# MicrocontrollerBoard_V0_2.net
KiCad netlist of a schematic drawn in EAGLE
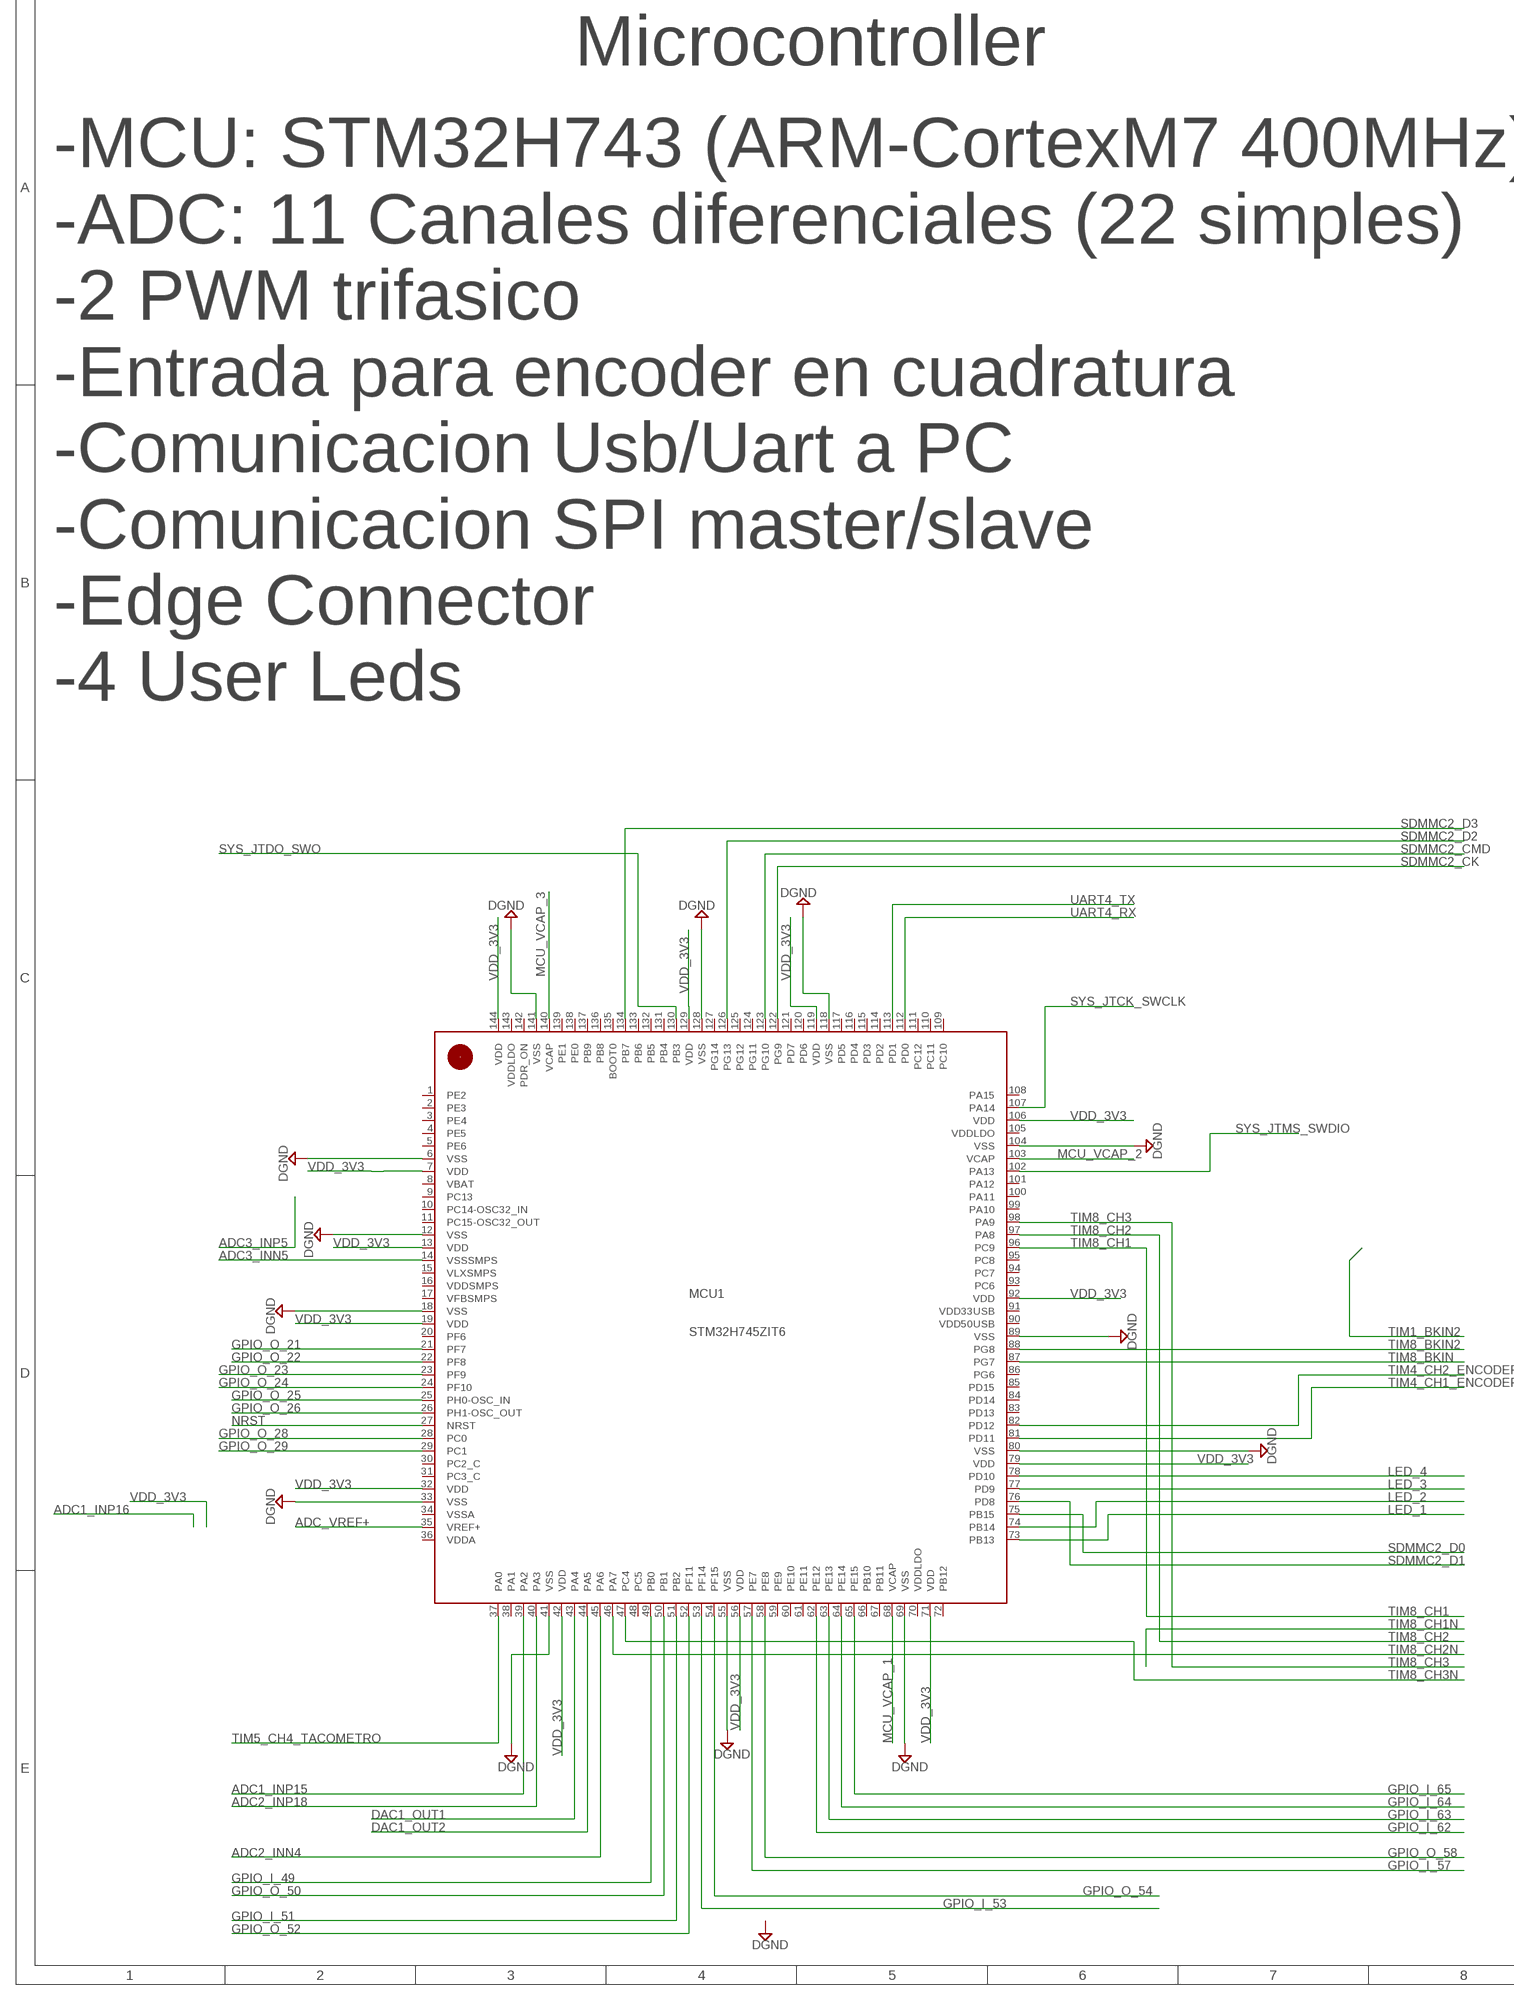
[diagram p0: schematic, sheet 1, part 1 of 2]
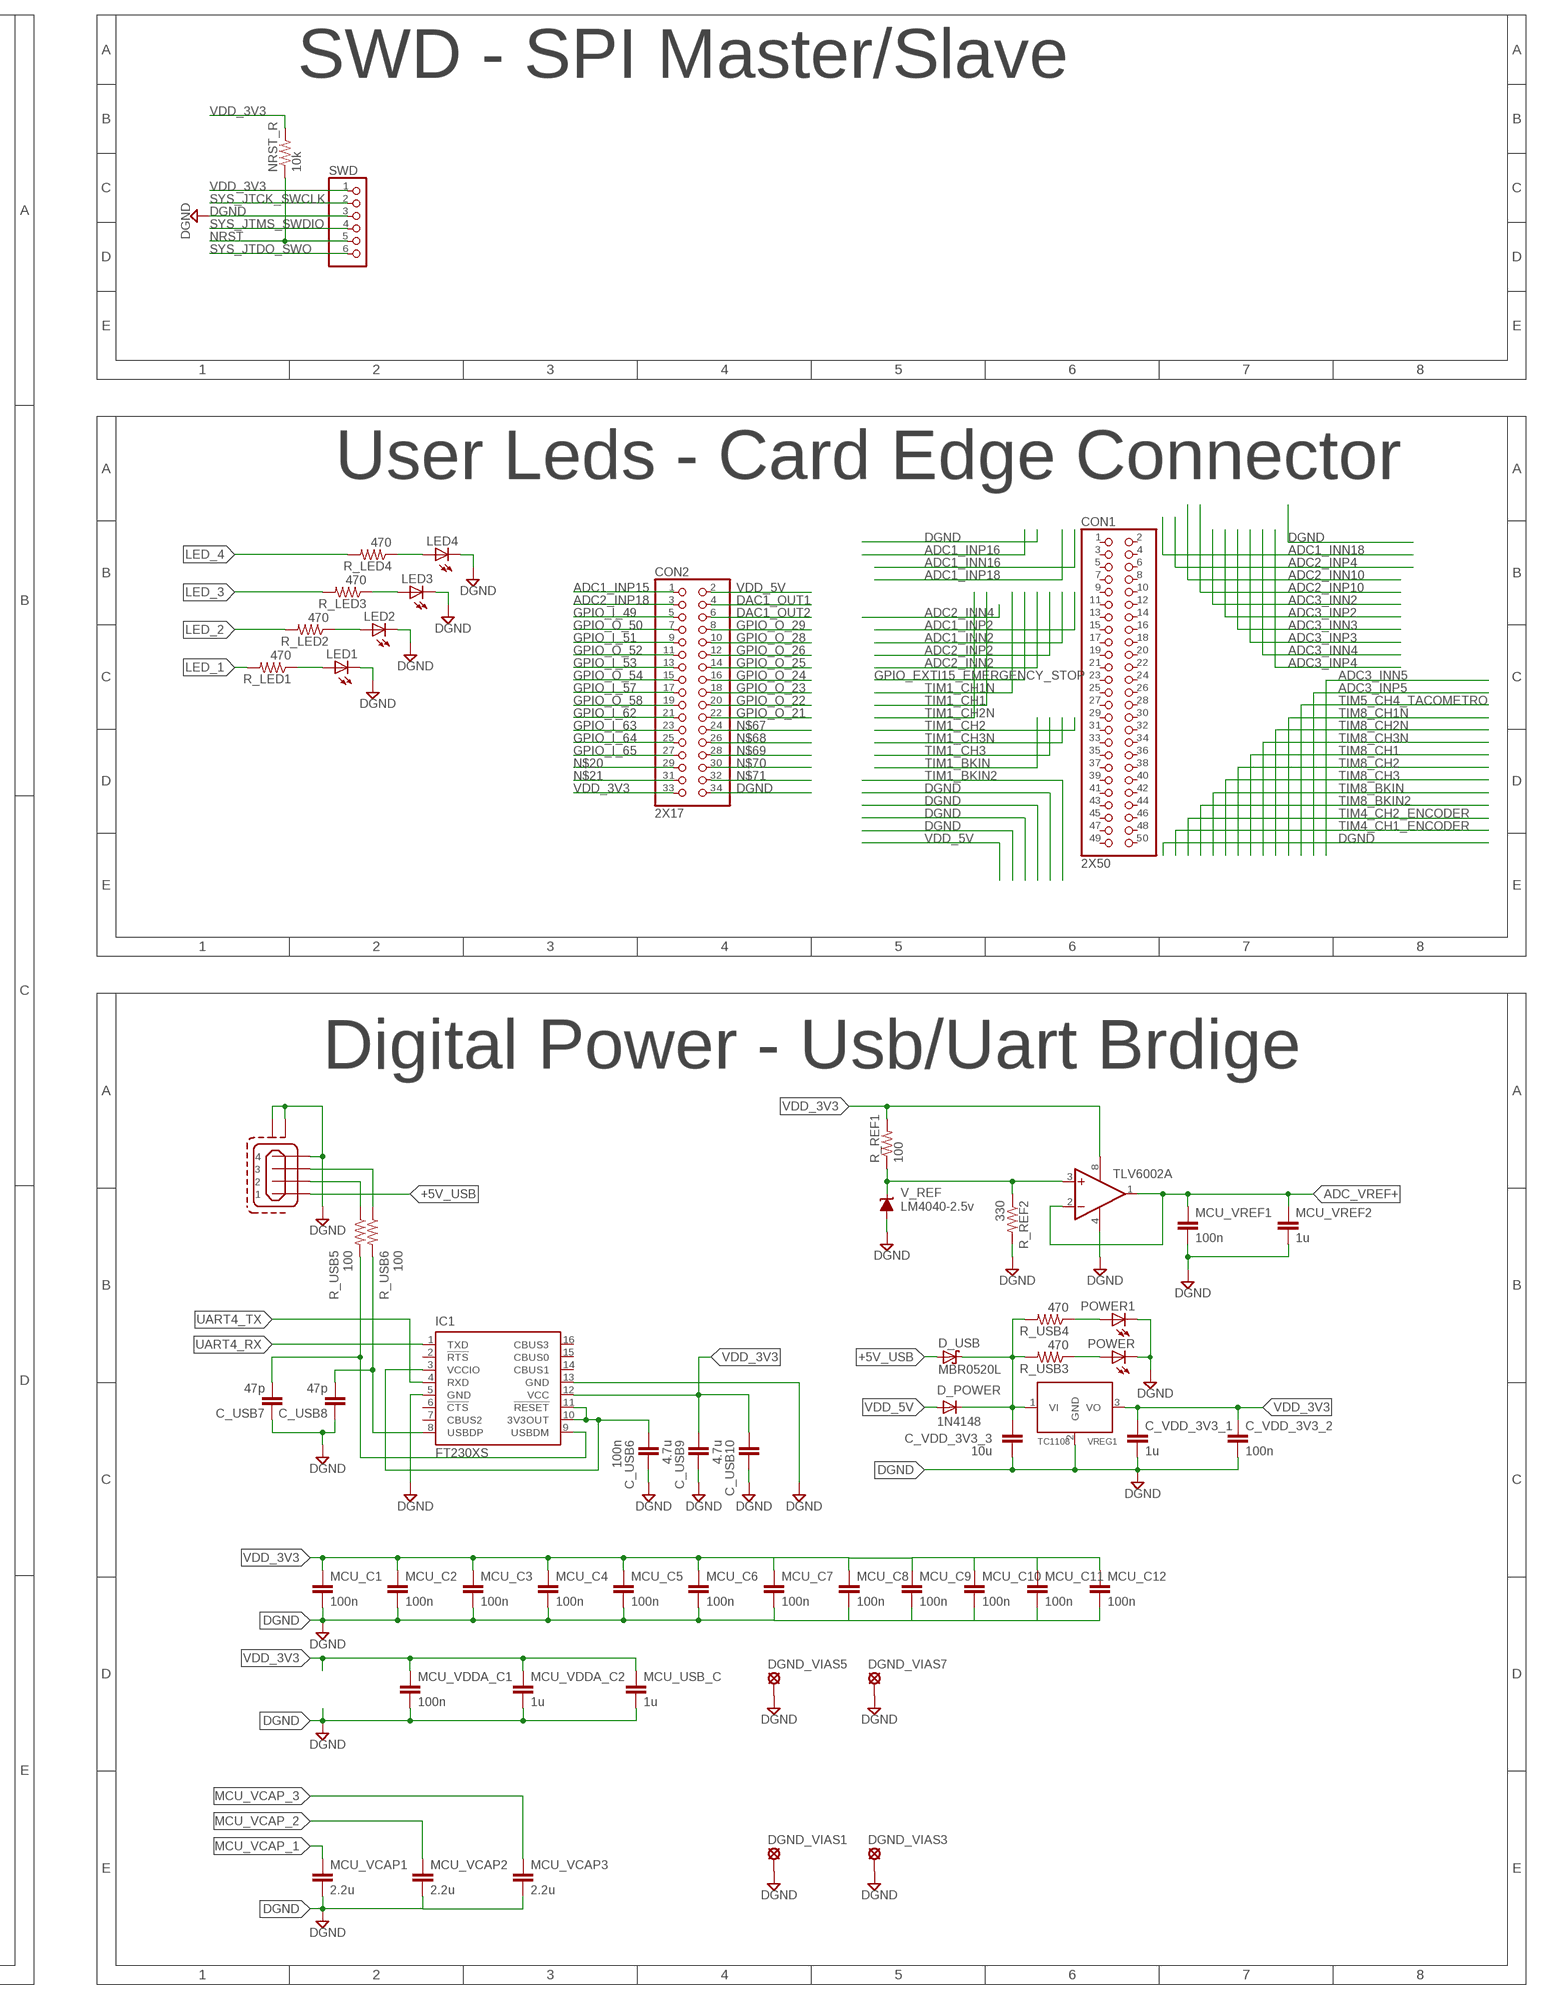
[diagram p1: schematic, sheet 1, part 2 of 2]

(export (version "E")
  (design (tool "Eeschema 10.0.6"))
  (components
    (comp (ref "CON1")
      (value "2X50")
      (footprint "eagle-import:2X25")
      (libsource (lib "eagle-import") (part "2X50"))
    )
    (comp (ref "CON2")
      (value "2X17")
      (footprint "eagle-import:2X17")
      (libsource (lib "eagle-import") (part "2X17"))
    )
    (comp (ref "C_USB6")
      (value "100n")
      (footprint "eagle-import:C0402")
      (libsource (lib "eagle-import") (part "C-EUC0402"))
    )
    (comp (ref "C_USB7")
      (value "47p")
      (footprint "eagle-import:C0402")
      (libsource (lib "eagle-import") (part "C-EUC0402"))
    )
    (comp (ref "C_USB8")
      (value "47p")
      (footprint "eagle-import:C0402")
      (libsource (lib "eagle-import") (part "C-EUC0402"))
    )
    (comp (ref "C_USB9")
      (value "4.7u")
      (footprint "eagle-import:C0402")
      (libsource (lib "eagle-import") (part "C-EUC0402"))
    )
    (comp (ref "C_USB10")
      (value "4.7u")
      (footprint "eagle-import:C0402")
      (libsource (lib "eagle-import") (part "C-EUC0402"))
    )
    (comp (ref "C_VDD_3V3_1")
      (value "1u")
      (footprint "eagle-import:C0603K")
      (libsource (lib "eagle-import") (part "C-EUC0603K"))
    )
    (comp (ref "C_VDD_3V3_2")
      (value "100n")
      (footprint "eagle-import:C0603K")
      (libsource (lib "eagle-import") (part "C-EUC0603K"))
    )
    (comp (ref "C_VDD_3V3_3")
      (value "10u")
      (footprint "eagle-import:C0603K")
      (libsource (lib "eagle-import") (part "C-EUC0603K"))
    )
    (comp (ref "DGND_VIAS1")
      (value "LSP10")
      (footprint "eagle-import:LSP10")
      (libsource (lib "eagle-import") (part "LSP10"))
    )
    (comp (ref "DGND_VIAS3")
      (value "LSP10")
      (footprint "eagle-import:LSP10")
      (libsource (lib "eagle-import") (part "LSP10"))
    )
    (comp (ref "DGND_VIAS5")
      (value "LSP10")
      (footprint "eagle-import:LSP10")
      (libsource (lib "eagle-import") (part "LSP10"))
    )
    (comp (ref "DGND_VIAS7")
      (value "LSP10")
      (footprint "eagle-import:LSP10")
      (libsource (lib "eagle-import") (part "LSP10"))
    )
    (comp (ref "D_POWER")
      (value "1N4148")
      (footprint "eagle-import:SMA-DO214AC")
      (libsource (lib "eagle-import") (part "GF1"))
    )
    (comp (ref "D_USB")
      (value "MBR0520L")
      (footprint "eagle-import:SOD-123")
      (libsource (lib "eagle-import") (part "MBR0520L"))
    )
    (comp (ref "IC1")
      (value "FT230XS")
      (footprint "eagle-import:SSOP16")
      (libsource (lib "eagle-import") (part "FT230XS"))
    )
    (comp (ref "LED1")
      (value "LEDCHIPLED_0805")
      (footprint "eagle-import:CHIPLED_0805")
      (libsource (lib "eagle-import") (part "LEDCHIPLED_0805"))
    )
    (comp (ref "LED2")
      (value "LEDCHIPLED_0805")
      (footprint "eagle-import:CHIPLED_0805")
      (libsource (lib "eagle-import") (part "LEDCHIPLED_0805"))
    )
    (comp (ref "LED3")
      (value "LEDCHIPLED_0805")
      (footprint "eagle-import:CHIPLED_0805")
      (libsource (lib "eagle-import") (part "LEDCHIPLED_0805"))
    )
    (comp (ref "LED4")
      (value "LEDCHIPLED_0805")
      (footprint "eagle-import:CHIPLED_0805")
      (libsource (lib "eagle-import") (part "LEDCHIPLED_0805"))
    )
    (comp (ref "MCU1")
      (value "STM32H745ZIT6144")
      (footprint "eagle-import:LQFP144")
      (libsource (lib "eagle-import") (part "STM32H745ZIT6144"))
    )
    (comp (ref "MCU_C1")
      (value "100n")
      (footprint "eagle-import:C0402")
      (libsource (lib "eagle-import") (part "C-EUC0402"))
    )
    (comp (ref "MCU_C2")
      (value "100n")
      (footprint "eagle-import:C0402")
      (libsource (lib "eagle-import") (part "C-EUC0402"))
    )
    (comp (ref "MCU_C3")
      (value "100n")
      (footprint "eagle-import:C0402")
      (libsource (lib "eagle-import") (part "C-EUC0402"))
    )
    (comp (ref "MCU_C4")
      (value "100n")
      (footprint "eagle-import:C0402")
      (libsource (lib "eagle-import") (part "C-EUC0402"))
    )
    (comp (ref "MCU_C5")
      (value "100n")
      (footprint "eagle-import:C0402")
      (libsource (lib "eagle-import") (part "C-EUC0402"))
    )
    (comp (ref "MCU_C6")
      (value "100n")
      (footprint "eagle-import:C0402")
      (libsource (lib "eagle-import") (part "C-EUC0402"))
    )
    (comp (ref "MCU_C7")
      (value "100n")
      (footprint "eagle-import:C0402")
      (libsource (lib "eagle-import") (part "C-EUC0402"))
    )
    (comp (ref "MCU_C8")
      (value "100n")
      (footprint "eagle-import:C0402")
      (libsource (lib "eagle-import") (part "C-EUC0402"))
    )
    (comp (ref "MCU_C9")
      (value "100n")
      (footprint "eagle-import:C0402")
      (libsource (lib "eagle-import") (part "C-EUC0402"))
    )
    (comp (ref "MCU_C10")
      (value "100n")
      (footprint "eagle-import:C0402")
      (libsource (lib "eagle-import") (part "C-EUC0402"))
    )
    (comp (ref "MCU_C11")
      (value "100n")
      (footprint "eagle-import:C0402")
      (libsource (lib "eagle-import") (part "C-EUC0402"))
    )
    (comp (ref "MCU_C12")
      (value "100n")
      (footprint "eagle-import:C0402")
      (libsource (lib "eagle-import") (part "C-EUC0402"))
    )
    (comp (ref "MCU_USB_C")
      (value "1u")
      (footprint "eagle-import:C0402")
      (libsource (lib "eagle-import") (part "C-EUC0402"))
    )
    (comp (ref "MCU_VCAP1")
      (value "2.2u")
      (footprint "eagle-import:C0402")
      (libsource (lib "eagle-import") (part "C-EUC0402"))
    )
    (comp (ref "MCU_VCAP2")
      (value "2.2u")
      (footprint "eagle-import:C0402")
      (libsource (lib "eagle-import") (part "C-EUC0402"))
    )
    (comp (ref "MCU_VCAP3")
      (value "2.2u")
      (footprint "eagle-import:C0402")
      (libsource (lib "eagle-import") (part "C-EUC0402"))
    )
    (comp (ref "MCU_VDDA_C1")
      (value "100n")
      (footprint "eagle-import:C0402")
      (libsource (lib "eagle-import") (part "C-EUC0402"))
    )
    (comp (ref "MCU_VDDA_C2")
      (value "1u")
      (footprint "eagle-import:C0402")
      (libsource (lib "eagle-import") (part "C-EUC0402"))
    )
    (comp (ref "MCU_VREF1")
      (value "100n")
      (footprint "eagle-import:C0402")
      (libsource (lib "eagle-import") (part "C-EUC0402"))
    )
    (comp (ref "MCU_VREF2")
      (value "1u")
      (footprint "eagle-import:C0402")
      (libsource (lib "eagle-import") (part "C-EUC0402"))
    )
    (comp (ref "NRST_R")
      (value "10k")
      (footprint "eagle-import:R0402")
      (libsource (lib "eagle-import") (part "R-US_R0402"))
    )
    (comp (ref "POWER")
      (value "LEDCHIPLED_0805")
      (footprint "eagle-import:CHIPLED_0805")
      (libsource (lib "eagle-import") (part "LEDCHIPLED_0805"))
    )
    (comp (ref "POWER1")
      (value "LEDCHIPLED_0805")
      (footprint "eagle-import:CHIPLED_0805")
      (libsource (lib "eagle-import") (part "LEDCHIPLED_0805"))
    )
    (comp (ref "R_LED1")
      (value "470")
      (footprint "eagle-import:R0402")
      (libsource (lib "eagle-import") (part "R-US_R0402"))
    )
    (comp (ref "R_LED2")
      (value "470")
      (footprint "eagle-import:R0402")
      (libsource (lib "eagle-import") (part "R-US_R0402"))
    )
    (comp (ref "R_LED3")
      (value "470")
      (footprint "eagle-import:R0402")
      (libsource (lib "eagle-import") (part "R-US_R0402"))
    )
    (comp (ref "R_LED4")
      (value "470")
      (footprint "eagle-import:R0402")
      (libsource (lib "eagle-import") (part "R-US_R0402"))
    )
    (comp (ref "R_REF1")
      (value "100")
      (footprint "eagle-import:R0805")
      (libsource (lib "eagle-import") (part "R-US_R0805"))
    )
    (comp (ref "R_REF2")
      (value "330")
      (footprint "eagle-import:R0805")
      (libsource (lib "eagle-import") (part "R-US_R0805"))
    )
    (comp (ref "R_USB3")
      (value "470")
      (footprint "eagle-import:R0402")
      (libsource (lib "eagle-import") (part "R-US_R0402"))
    )
    (comp (ref "R_USB4")
      (value "470")
      (footprint "eagle-import:R0402")
      (libsource (lib "eagle-import") (part "R-US_R0402"))
    )
    (comp (ref "R_USB5")
      (value "100")
      (footprint "eagle-import:R0402")
      (libsource (lib "eagle-import") (part "R-US_R0402"))
    )
    (comp (ref "R_USB6")
      (value "100")
      (footprint "eagle-import:R0402")
      (libsource (lib "eagle-import") (part "R-US_R0402"))
    )
    (comp (ref "SWD")
      (value "PINHD-1X6/90")
      (footprint "eagle-import:1X06_90")
      (libsource (lib "eagle-import") (part "PINHD-1X6/90"))
    )
    (comp (ref "TLV6002")
      (value "TL082D")
      (footprint "eagle-import:SO08")
      (libsource (lib "eagle-import") (part "TL082D"))
    )
    (comp (ref "VREG1")
      (value "TC1108'SOT-223'")
      (footprint "eagle-import:SOT-223")
      (libsource (lib "eagle-import") (part "TC1108'SOT-223'"))
    )
    (comp (ref "V_REF")
      (value "LM4040-2.5v")
      (footprint "eagle-import:DBZ_R-PDSO-G3")
      (fields (field (name "MPN") "LM4041A12IDBZR"))
      (libsource (lib "eagle-import") (part "LM4041DBZA12"))
    )
    (comp (ref "X2")
      (value "MINI-USB_SHIELD4P-85-32004-00X")
      (footprint "eagle-import:85-32004-00X")
      (libsource (lib "eagle-import") (part "MINI-USB_SHIELD4P-85-32004-00X"))
    )
  )
  (nets
    (net (code "1") (name "+5V_USB") (class "Default")
      (node (ref "D_USB") (pin "A") (pinfunction "IN_A") (pintype "passive"))
      (node (ref "X2") (pin "1") (pinfunction "1_1") (pintype "passive"))
    )
    (net (code "6") (name "/ADC1_INP15") (class "Default")
      (node (ref "CON2") (pin "1") (pinfunction "1_1") (pintype "passive"))
      (node (ref "MCU1") (pin "39") (pinfunction "PA2_39") (pintype "bidirectional"))
    )
    (net (code "10") (name "/ADC2_INN4") (class "Default")
      (node (ref "MCU1") (pin "45") (pinfunction "PA6_45") (pintype "bidirectional"))
    )
    (net (code "15") (name "/ADC2_INP18") (class "Default")
      (node (ref "CON2") (pin "3") (pinfunction "3_3") (pintype "passive"))
      (node (ref "MCU1") (pin "40") (pinfunction "PA3_40") (pintype "bidirectional"))
    )
    (net (code "19") (name "/ADC3_INN5") (class "Default")
      (node (ref "MCU1") (pin "14") (pinfunction "VSSSMPS_14") (pintype "bidirectional"))
    )
    (net (code "24") (name "/DAC1_OUT1") (class "Default")
      (node (ref "CON2") (pin "4") (pinfunction "4_4") (pintype "passive"))
      (node (ref "MCU1") (pin "43") (pinfunction "PA4_43") (pintype "bidirectional"))
    )
    (net (code "25") (name "/DAC1_OUT2") (class "Default")
      (node (ref "CON2") (pin "6") (pinfunction "6_6") (pintype "passive"))
      (node (ref "MCU1") (pin "44") (pinfunction "PA5_44") (pintype "bidirectional"))
    )
    (net (code "27") (name "/GPIO_I_49") (class "Default")
      (node (ref "CON2") (pin "5") (pinfunction "5_5") (pintype "passive"))
      (node (ref "MCU1") (pin "49") (pinfunction "PB0_49") (pintype "bidirectional"))
    )
    (net (code "28") (name "/GPIO_I_51") (class "Default")
      (node (ref "CON2") (pin "9") (pinfunction "9_9") (pintype "passive"))
      (node (ref "MCU1") (pin "51") (pinfunction "PB2_51") (pintype "bidirectional"))
    )
    (net (code "29") (name "/GPIO_I_53") (class "Default")
      (node (ref "CON2") (pin "13") (pinfunction "13_13") (pintype "passive"))
      (node (ref "MCU1") (pin "53") (pinfunction "PF14_53") (pintype "bidirectional"))
    )
    (net (code "30") (name "/GPIO_I_57") (class "Default")
      (node (ref "CON2") (pin "17") (pinfunction "17_17") (pintype "passive"))
      (node (ref "MCU1") (pin "57") (pinfunction "PE7_57") (pintype "bidirectional"))
    )
    (net (code "31") (name "/GPIO_I_62") (class "Default")
      (node (ref "CON2") (pin "21") (pinfunction "21_21") (pintype "passive"))
      (node (ref "MCU1") (pin "62") (pinfunction "PE12_62") (pintype "bidirectional"))
    )
    (net (code "32") (name "/GPIO_I_63") (class "Default")
      (node (ref "CON2") (pin "23") (pinfunction "23_23") (pintype "passive"))
      (node (ref "MCU1") (pin "63") (pinfunction "PE13_63") (pintype "bidirectional"))
    )
    (net (code "33") (name "/GPIO_I_64") (class "Default")
      (node (ref "CON2") (pin "25") (pinfunction "25_25") (pintype "passive"))
      (node (ref "MCU1") (pin "64") (pinfunction "PE14_64") (pintype "bidirectional"))
    )
    (net (code "34") (name "/GPIO_I_65") (class "Default")
      (node (ref "CON2") (pin "27") (pinfunction "27_27") (pintype "passive"))
      (node (ref "MCU1") (pin "65") (pinfunction "PE15_65") (pintype "bidirectional"))
    )
    (net (code "35") (name "/GPIO_O_21") (class "Default")
      (node (ref "CON2") (pin "22") (pinfunction "22_22") (pintype "passive"))
      (node (ref "MCU1") (pin "21") (pinfunction "PF7_21") (pintype "bidirectional"))
    )
    (net (code "36") (name "/GPIO_O_22") (class "Default")
      (node (ref "CON2") (pin "20") (pinfunction "20_20") (pintype "passive"))
      (node (ref "MCU1") (pin "22") (pinfunction "PF8_22") (pintype "bidirectional"))
    )
    (net (code "37") (name "/GPIO_O_23") (class "Default")
      (node (ref "CON2") (pin "18") (pinfunction "18_18") (pintype "passive"))
      (node (ref "MCU1") (pin "23") (pinfunction "PF9_23") (pintype "bidirectional"))
    )
    (net (code "38") (name "/GPIO_O_24") (class "Default")
      (node (ref "CON2") (pin "16") (pinfunction "16_16") (pintype "passive"))
      (node (ref "MCU1") (pin "24") (pinfunction "PF10_24") (pintype "bidirectional"))
    )
    (net (code "39") (name "/GPIO_O_25") (class "Default")
      (node (ref "CON2") (pin "14") (pinfunction "14_14") (pintype "passive"))
      (node (ref "MCU1") (pin "25") (pinfunction "PH0-OSC_IN_25") (pintype "bidirectional"))
    )
    (net (code "40") (name "/GPIO_O_26") (class "Default")
      (node (ref "CON2") (pin "12") (pinfunction "12_12") (pintype "passive"))
      (node (ref "MCU1") (pin "26") (pinfunction "PH1-OSC_OUT_26") (pintype "bidirectional"))
    )
    (net (code "41") (name "/GPIO_O_28") (class "Default")
      (node (ref "CON2") (pin "10") (pinfunction "10_10") (pintype "passive"))
      (node (ref "MCU1") (pin "28") (pinfunction "PC0_28") (pintype "bidirectional"))
    )
    (net (code "42") (name "/GPIO_O_29") (class "Default")
      (node (ref "CON2") (pin "8") (pinfunction "8_8") (pintype "passive"))
      (node (ref "MCU1") (pin "29") (pinfunction "PC1_29") (pintype "bidirectional"))
    )
    (net (code "43") (name "/GPIO_O_50") (class "Default")
      (node (ref "CON2") (pin "7") (pinfunction "7_7") (pintype "passive"))
      (node (ref "MCU1") (pin "50") (pinfunction "PB1_50") (pintype "bidirectional"))
    )
    (net (code "44") (name "/GPIO_O_52") (class "Default")
      (node (ref "CON2") (pin "11") (pinfunction "11_11") (pintype "passive"))
      (node (ref "MCU1") (pin "52") (pinfunction "PF11_52") (pintype "bidirectional"))
    )
    (net (code "45") (name "/GPIO_O_54") (class "Default")
      (node (ref "CON2") (pin "15") (pinfunction "15_15") (pintype "passive"))
      (node (ref "MCU1") (pin "54") (pinfunction "PF15_54") (pintype "bidirectional"))
    )
    (net (code "46") (name "/GPIO_O_58") (class "Default")
      (node (ref "CON2") (pin "19") (pinfunction "19_19") (pintype "passive"))
      (node (ref "MCU1") (pin "58") (pinfunction "PE8_58") (pintype "bidirectional"))
    )
    (net (code "47") (name "/N$20") (class "Default")
      (node (ref "CON2") (pin "29") (pinfunction "29_29") (pintype "passive"))
    )
    (net (code "48") (name "/N$21") (class "Default")
      (node (ref "CON2") (pin "31") (pinfunction "31_31") (pintype "passive"))
    )
    (net (code "49") (name "/N$67") (class "Default")
      (node (ref "CON2") (pin "24") (pinfunction "24_24") (pintype "passive"))
    )
    (net (code "50") (name "/N$68") (class "Default")
      (node (ref "CON2") (pin "26") (pinfunction "26_26") (pintype "passive"))
    )
    (net (code "51") (name "/N$69") (class "Default")
      (node (ref "CON2") (pin "28") (pinfunction "28_28") (pintype "passive"))
    )
    (net (code "52") (name "/N$70") (class "Default")
      (node (ref "CON2") (pin "30") (pinfunction "30_30") (pintype "passive"))
    )
    (net (code "53") (name "/N$71") (class "Default")
      (node (ref "CON2") (pin "32") (pinfunction "32_32") (pintype "passive"))
    )
    (net (code "54") (name "/NRST") (class "Default")
      (node (ref "MCU1") (pin "27") (pinfunction "NRST_27") (pintype "bidirectional"))
      (node (ref "NRST_R") (pin "1") (pinfunction "1_1") (pintype "passive"))
      (node (ref "SWD") (pin "5") (pinfunction "5_5") (pintype "passive"))
    )
    (net (code "55") (name "/SDMMC2_CK") (class "Default")
      (node (ref "MCU1") (pin "122") (pinfunction "PG9_122") (pintype "bidirectional"))
    )
    (net (code "56") (name "/SDMMC2_CMD") (class "Default")
      (node (ref "MCU1") (pin "123") (pinfunction "PG10_123") (pintype "bidirectional"))
    )
    (net (code "57") (name "/SDMMC2_D0") (class "Default")
      (node (ref "MCU1") (pin "75") (pinfunction "PB15_75") (pintype "bidirectional"))
    )
    (net (code "58") (name "/SDMMC2_D1") (class "Default")
      (node (ref "MCU1") (pin "76") (pinfunction "PD8_76") (pintype "bidirectional"))
    )
    (net (code "59") (name "/SDMMC2_D2") (class "Default")
      (node (ref "MCU1") (pin "126") (pinfunction "PG13_126") (pintype "bidirectional"))
    )
    (net (code "60") (name "/SDMMC2_D3") (class "Default")
      (node (ref "MCU1") (pin "134") (pinfunction "PB7_134") (pintype "bidirectional"))
    )
    (net (code "61") (name "/SYS_JTCK_SWCLK") (class "Default")
      (node (ref "MCU1") (pin "107") (pinfunction "PA14_107") (pintype "bidirectional"))
      (node (ref "SWD") (pin "2") (pinfunction "2_2") (pintype "passive"))
    )
    (net (code "62") (name "/SYS_JTDO_SWO") (class "Default")
      (node (ref "MCU1") (pin "130") (pinfunction "PB3_130") (pintype "bidirectional"))
      (node (ref "SWD") (pin "6") (pinfunction "6_6") (pintype "passive"))
    )
    (net (code "63") (name "/SYS_JTMS_SWDIO") (class "Default")
      (node (ref "MCU1") (pin "102") (pinfunction "PA13_102") (pintype "bidirectional"))
      (node (ref "SWD") (pin "4") (pinfunction "4_4") (pintype "passive"))
    )
    (net (code "72") (name "/TIM4_CH1_ENCODER") (class "Default")
      (node (ref "MCU1") (pin "81") (pinfunction "PD11_81") (pintype "bidirectional"))
    )
    (net (code "73") (name "/TIM4_CH2_ENCODER") (class "Default")
      (node (ref "MCU1") (pin "82") (pinfunction "PD12_82") (pintype "bidirectional"))
    )
    (net (code "74") (name "/TIM5_CH4_TACOMETRO") (class "Default")
      (node (ref "MCU1") (pin "37") (pinfunction "PA0_37") (pintype "bidirectional"))
    )
    (net (code "75") (name "/TIM8_BKIN") (class "Default")
      (node (ref "MCU1") (pin "87") (pinfunction "PG7_87") (pintype "bidirectional"))
    )
    (net (code "76") (name "/TIM8_BKIN2") (class "Default")
      (node (ref "MCU1") (pin "88") (pinfunction "PG8_88") (pintype "bidirectional"))
    )
    (net (code "77") (name "/TIM8_CH1") (class "Default")
      (node (ref "MCU1") (pin "96") (pinfunction "PC9_96") (pintype "bidirectional"))
    )
    (net (code "79") (name "/TIM8_CH2") (class "Default")
      (node (ref "MCU1") (pin "97") (pinfunction "PA8_97") (pintype "bidirectional"))
    )
    (net (code "80") (name "/TIM8_CH2N") (class "Default")
      (node (ref "MCU1") (pin "46") (pinfunction "PA7_46") (pintype "bidirectional"))
    )
    (net (code "81") (name "/TIM8_CH3") (class "Default")
      (node (ref "MCU1") (pin "98") (pinfunction "PA9_98") (pintype "bidirectional"))
    )
    (net (code "82") (name "/TIM8_CH3N") (class "Default")
      (node (ref "MCU1") (pin "47") (pinfunction "PC4_47") (pintype "bidirectional"))
    )
    (net (code "83") (name "ADC_VREF+") (class "Default")
      (node (ref "MCU1") (pin "35") (pinfunction "VREF+_35") (pintype "bidirectional"))
      (node (ref "MCU_VREF1") (pin "1") (pinfunction "1_1") (pintype "passive"))
      (node (ref "MCU_VREF2") (pin "1") (pinfunction "1_1") (pintype "passive"))
      (node (ref "TLV6002") (pin "1") (pinfunction "OUT_1") (pintype "output"))
      (node (ref "TLV6002") (pin "2") (pinfunction "-IN_2") (pintype "input"))
    )
    (net (code "84") (name "DGND") (class "Default")
      (node (ref "CON2") (pin "34") (pinfunction "34_34") (pintype "passive"))
      (node (ref "C_USB10") (pin "1") (pinfunction "1_1") (pintype "passive"))
      (node (ref "C_USB6") (pin "1") (pinfunction "1_1") (pintype "passive"))
      (node (ref "C_USB7") (pin "1") (pinfunction "1_1") (pintype "passive"))
      (node (ref "C_USB8") (pin "1") (pinfunction "1_1") (pintype "passive"))
      (node (ref "C_USB9") (pin "1") (pinfunction "1_1") (pintype "passive"))
      (node (ref "C_VDD_3V3_1") (pin "2") (pinfunction "2_2") (pintype "passive"))
      (node (ref "C_VDD_3V3_2") (pin "2") (pinfunction "2_2") (pintype "passive"))
      (node (ref "C_VDD_3V3_3") (pin "2") (pinfunction "2_2") (pintype "passive"))
      (node (ref "DGND_VIAS1") (pin "MP") (pinfunction "MP_MP") (pintype "passive"))
      (node (ref "DGND_VIAS3") (pin "MP") (pinfunction "MP_MP") (pintype "passive"))
      (node (ref "DGND_VIAS5") (pin "MP") (pinfunction "MP_MP") (pintype "passive"))
      (node (ref "DGND_VIAS7") (pin "MP") (pinfunction "MP_MP") (pintype "passive"))
      (node (ref "IC1") (pin "13") (pinfunction "GND_13") (pintype "power_in"))
      (node (ref "IC1") (pin "5") (pinfunction "GND_5") (pintype "power_in"))
      (node (ref "LED1") (pin "C") (pinfunction "C_C") (pintype "passive"))
      (node (ref "LED2") (pin "C") (pinfunction "C_C") (pintype "passive"))
      (node (ref "LED3") (pin "C") (pinfunction "C_C") (pintype "passive"))
      (node (ref "LED4") (pin "C") (pinfunction "C_C") (pintype "passive"))
      (node (ref "MCU1") (pin "104") (pinfunction "VSS_104") (pintype "bidirectional"))
      (node (ref "MCU1") (pin "118") (pinfunction "VSS_118") (pintype "bidirectional"))
      (node (ref "MCU1") (pin "12") (pinfunction "VSS_12") (pintype "bidirectional"))
      (node (ref "MCU1") (pin "128") (pinfunction "VSS_128") (pintype "bidirectional"))
      (node (ref "MCU1") (pin "141") (pinfunction "VSS_141") (pintype "bidirectional"))
      (node (ref "MCU1") (pin "18") (pinfunction "VSS_18") (pintype "bidirectional"))
      (node (ref "MCU1") (pin "33") (pinfunction "VSS_33") (pintype "bidirectional"))
      (node (ref "MCU1") (pin "41") (pinfunction "VSS_41") (pintype "bidirectional"))
      (node (ref "MCU1") (pin "55") (pinfunction "VSS_55") (pintype "bidirectional"))
      (node (ref "MCU1") (pin "6") (pinfunction "VSS_6") (pintype "bidirectional"))
      (node (ref "MCU1") (pin "69") (pinfunction "VSS_69") (pintype "bidirectional"))
      (node (ref "MCU1") (pin "80") (pinfunction "VSS_80") (pintype "bidirectional"))
      (node (ref "MCU1") (pin "89") (pinfunction "VSS_89") (pintype "bidirectional"))
      (node (ref "MCU_C1") (pin "2") (pinfunction "2_2") (pintype "passive"))
      (node (ref "MCU_C10") (pin "2") (pinfunction "2_2") (pintype "passive"))
      (node (ref "MCU_C11") (pin "2") (pinfunction "2_2") (pintype "passive"))
      (node (ref "MCU_C12") (pin "2") (pinfunction "2_2") (pintype "passive"))
      (node (ref "MCU_C2") (pin "2") (pinfunction "2_2") (pintype "passive"))
      (node (ref "MCU_C3") (pin "2") (pinfunction "2_2") (pintype "passive"))
      (node (ref "MCU_C4") (pin "2") (pinfunction "2_2") (pintype "passive"))
      (node (ref "MCU_C5") (pin "2") (pinfunction "2_2") (pintype "passive"))
      (node (ref "MCU_C6") (pin "2") (pinfunction "2_2") (pintype "passive"))
      (node (ref "MCU_C7") (pin "2") (pinfunction "2_2") (pintype "passive"))
      (node (ref "MCU_C8") (pin "2") (pinfunction "2_2") (pintype "passive"))
      (node (ref "MCU_C9") (pin "2") (pinfunction "2_2") (pintype "passive"))
      (node (ref "MCU_USB_C") (pin "2") (pinfunction "2_2") (pintype "passive"))
      (node (ref "MCU_VCAP1") (pin "2") (pinfunction "2_2") (pintype "passive"))
      (node (ref "MCU_VCAP2") (pin "2") (pinfunction "2_2") (pintype "passive"))
      (node (ref "MCU_VCAP3") (pin "2") (pinfunction "2_2") (pintype "passive"))
      (node (ref "MCU_VDDA_C1") (pin "2") (pinfunction "2_2") (pintype "passive"))
      (node (ref "MCU_VDDA_C2") (pin "2") (pinfunction "2_2") (pintype "passive"))
      (node (ref "MCU_VREF1") (pin "2") (pinfunction "2_2") (pintype "passive"))
      (node (ref "MCU_VREF2") (pin "2") (pinfunction "2_2") (pintype "passive"))
      (node (ref "POWER") (pin "C") (pinfunction "C_C") (pintype "passive"))
      (node (ref "POWER1") (pin "C") (pinfunction "C_C") (pintype "passive"))
      (node (ref "R_REF2") (pin "2") (pinfunction "2_2") (pintype "passive"))
      (node (ref "SWD") (pin "3") (pinfunction "3_3") (pintype "passive"))
      (node (ref "TLV6002") (pin "4") (pinfunction "V-_4") (pintype "power_in"))
      (node (ref "VREG1") (pin "2") (pinfunction "GND_2") (pintype "bidirectional"))
      (node (ref "V_REF") (pin "2") (pinfunction "A_2") (pintype "passive"))
      (node (ref "X2") (pin "4") (pinfunction "4_4") (pintype "passive"))
      (node (ref "X2") (pin "M1") (pinfunction "S1_M1") (pintype "passive"))
      (node (ref "X2") (pin "M2") (pinfunction "S2_M2") (pintype "passive"))
    )
    (net (code "85") (name "LED_1") (class "Default")
      (node (ref "MCU1") (pin "73") (pinfunction "PB13_73") (pintype "bidirectional"))
      (node (ref "R_LED1") (pin "2") (pinfunction "2_2") (pintype "passive"))
    )
    (net (code "86") (name "LED_2") (class "Default")
      (node (ref "MCU1") (pin "74") (pinfunction "PB14_74") (pintype "bidirectional"))
      (node (ref "R_LED2") (pin "2") (pinfunction "2_2") (pintype "passive"))
    )
    (net (code "87") (name "LED_3") (class "Default")
      (node (ref "MCU1") (pin "77") (pinfunction "PD9_77") (pintype "bidirectional"))
      (node (ref "R_LED3") (pin "2") (pinfunction "2_2") (pintype "passive"))
    )
    (net (code "88") (name "LED_4") (class "Default")
      (node (ref "MCU1") (pin "78") (pinfunction "PD10_78") (pintype "bidirectional"))
      (node (ref "R_LED4") (pin "2") (pinfunction "2_2") (pintype "passive"))
    )
    (net (code "89") (name "MCU_VCAP_1") (class "Default")
      (node (ref "MCU1") (pin "68") (pinfunction "VCAP_68") (pintype "bidirectional"))
      (node (ref "MCU_VCAP1") (pin "1") (pinfunction "1_1") (pintype "passive"))
    )
    (net (code "90") (name "MCU_VCAP_2") (class "Default")
      (node (ref "MCU1") (pin "103") (pinfunction "VCAP_103") (pintype "bidirectional"))
      (node (ref "MCU_VCAP2") (pin "1") (pinfunction "1_1") (pintype "passive"))
    )
    (net (code "91") (name "MCU_VCAP_3") (class "Default")
      (node (ref "MCU1") (pin "140") (pinfunction "VCAP_140") (pintype "bidirectional"))
      (node (ref "MCU_VCAP3") (pin "1") (pinfunction "1_1") (pintype "passive"))
    )
    (net (code "92") (name "Net-(D_POWER-C)") (class "Default")
      (node (ref "C_VDD_3V3_3") (pin "1") (pinfunction "1_1") (pintype "passive"))
      (node (ref "D_POWER") (pin "K") (pinfunction "C_K") (pintype "passive"))
      (node (ref "D_USB") (pin "C") (pinfunction "OUT_C") (pintype "passive"))
      (node (ref "R_USB3") (pin "2") (pinfunction "2_2") (pintype "passive"))
      (node (ref "R_USB4") (pin "2") (pinfunction "2_2") (pintype "passive"))
      (node (ref "VREG1") (pin "1") (pinfunction "VI_1") (pintype "bidirectional"))
    )
    (net (code "93") (name "Net-(IC1-3V3OUT)") (class "Default")
      (node (ref "C_USB6") (pin "2") (pinfunction "2_2") (pintype "passive"))
      (node (ref "IC1") (pin "10") (pinfunction "3V3OUT_10") (pintype "output"))
      (node (ref "IC1") (pin "11") (pinfunction "~{RESET}_11") (pintype "input"))
      (node (ref "IC1") (pin "3") (pinfunction "VCCIO_3") (pintype "power_in"))
    )
    (net (code "94") (name "Net-(IC1-USBDM)") (class "Default")
      (node (ref "C_USB7") (pin "2") (pinfunction "2_2") (pintype "passive"))
      (node (ref "IC1") (pin "9") (pinfunction "USBDM_9") (pintype "input"))
      (node (ref "R_USB5") (pin "2") (pinfunction "2_2") (pintype "passive"))
    )
    (net (code "95") (name "Net-(IC1-USBDP)") (class "Default")
      (node (ref "C_USB8") (pin "2") (pinfunction "2_2") (pintype "passive"))
      (node (ref "IC1") (pin "8") (pinfunction "USBDP_8") (pintype "input"))
      (node (ref "R_USB6") (pin "2") (pinfunction "2_2") (pintype "passive"))
    )
    (net (code "96") (name "Net-(LED1-PadA)") (class "Default")
      (node (ref "LED1") (pin "A") (pinfunction "A_A") (pintype "passive"))
      (node (ref "R_LED1") (pin "1") (pinfunction "1_1") (pintype "passive"))
    )
    (net (code "97") (name "Net-(LED2-PadA)") (class "Default")
      (node (ref "LED2") (pin "A") (pinfunction "A_A") (pintype "passive"))
      (node (ref "R_LED2") (pin "1") (pinfunction "1_1") (pintype "passive"))
    )
    (net (code "98") (name "Net-(LED3-PadA)") (class "Default")
      (node (ref "LED3") (pin "A") (pinfunction "A_A") (pintype "passive"))
      (node (ref "R_LED3") (pin "1") (pinfunction "1_1") (pintype "passive"))
    )
    (net (code "99") (name "Net-(LED4-PadA)") (class "Default")
      (node (ref "LED4") (pin "A") (pinfunction "A_A") (pintype "passive"))
      (node (ref "R_LED4") (pin "1") (pinfunction "1_1") (pintype "passive"))
    )
    (net (code "100") (name "Net-(POWER-PadA)") (class "Default")
      (node (ref "POWER") (pin "A") (pinfunction "A_A") (pintype "passive"))
      (node (ref "R_USB3") (pin "1") (pinfunction "1_1") (pintype "passive"))
    )
    (net (code "101") (name "Net-(POWER1-PadA)") (class "Default")
      (node (ref "POWER1") (pin "A") (pinfunction "A_A") (pintype "passive"))
      (node (ref "R_USB4") (pin "1") (pinfunction "1_1") (pintype "passive"))
    )
    (net (code "102") (name "Net-(R_USB5-Pad1)") (class "Default")
      (node (ref "R_USB5") (pin "1") (pinfunction "1_1") (pintype "passive"))
      (node (ref "X2") (pin "2") (pinfunction "2_2") (pintype "passive"))
    )
    (net (code "103") (name "Net-(R_USB6-Pad1)") (class "Default")
      (node (ref "R_USB6") (pin "1") (pinfunction "1_1") (pintype "passive"))
      (node (ref "X2") (pin "3") (pinfunction "3_3") (pintype "passive"))
    )
    (net (code "104") (name "Net-(TLV6002A-+IN)") (class "Default")
      (node (ref "R_REF1") (pin "1") (pinfunction "1_1") (pintype "passive"))
      (node (ref "R_REF2") (pin "1") (pinfunction "1_1") (pintype "passive"))
      (node (ref "TLV6002") (pin "3") (pinfunction "+IN_3") (pintype "input"))
      (node (ref "V_REF") (pin "1") (pinfunction "C_1") (pintype "passive"))
    )
    (net (code "105") (name "UART4_RX") (class "Default")
      (node (ref "IC1") (pin "1") (pinfunction "TXD_1") (pintype "output"))
      (node (ref "MCU1") (pin "112") (pinfunction "PD0_112") (pintype "bidirectional"))
    )
    (net (code "106") (name "UART4_TX") (class "Default")
      (node (ref "IC1") (pin "4") (pinfunction "RXD_4") (pintype "input"))
      (node (ref "MCU1") (pin "113") (pinfunction "PD1_113") (pintype "bidirectional"))
    )
    (net (code "107") (name "VDD_3V3") (class "Default")
      (node (ref "CON2") (pin "33") (pinfunction "33_33") (pintype "passive"))
      (node (ref "C_USB10") (pin "2") (pinfunction "2_2") (pintype "passive"))
      (node (ref "C_USB9") (pin "2") (pinfunction "2_2") (pintype "passive"))
      (node (ref "C_VDD_3V3_1") (pin "1") (pinfunction "1_1") (pintype "passive"))
      (node (ref "C_VDD_3V3_2") (pin "1") (pinfunction "1_1") (pintype "passive"))
      (node (ref "IC1") (pin "12") (pinfunction "VCC_12") (pintype "power_in"))
      (node (ref "MCU1") (pin "106") (pinfunction "VDD_106") (pintype "bidirectional"))
      (node (ref "MCU1") (pin "119") (pinfunction "VDD_119") (pintype "bidirectional"))
      (node (ref "MCU1") (pin "129") (pinfunction "VDD_129") (pintype "bidirectional"))
      (node (ref "MCU1") (pin "13") (pinfunction "VDD_13") (pintype "bidirectional"))
      (node (ref "MCU1") (pin "144") (pinfunction "VDD_144") (pintype "bidirectional"))
      (node (ref "MCU1") (pin "19") (pinfunction "VDD_19") (pintype "bidirectional"))
      (node (ref "MCU1") (pin "32") (pinfunction "VDD_32") (pintype "bidirectional"))
      (node (ref "MCU1") (pin "42") (pinfunction "VDD_42") (pintype "bidirectional"))
      (node (ref "MCU1") (pin "56") (pinfunction "VDD_56") (pintype "bidirectional"))
      (node (ref "MCU1") (pin "7") (pinfunction "VDD_7") (pintype "bidirectional"))
      (node (ref "MCU1") (pin "71") (pinfunction "VDD_71") (pintype "bidirectional"))
      (node (ref "MCU1") (pin "79") (pinfunction "VDD_79") (pintype "bidirectional"))
      (node (ref "MCU1") (pin "92") (pinfunction "VDD_92") (pintype "bidirectional"))
      (node (ref "MCU_C1") (pin "1") (pinfunction "1_1") (pintype "passive"))
      (node (ref "MCU_C10") (pin "1") (pinfunction "1_1") (pintype "passive"))
      (node (ref "MCU_C11") (pin "1") (pinfunction "1_1") (pintype "passive"))
      (node (ref "MCU_C12") (pin "1") (pinfunction "1_1") (pintype "passive"))
      (node (ref "MCU_C2") (pin "1") (pinfunction "1_1") (pintype "passive"))
      (node (ref "MCU_C3") (pin "1") (pinfunction "1_1") (pintype "passive"))
      (node (ref "MCU_C4") (pin "1") (pinfunction "1_1") (pintype "passive"))
      (node (ref "MCU_C5") (pin "1") (pinfunction "1_1") (pintype "passive"))
      (node (ref "MCU_C6") (pin "1") (pinfunction "1_1") (pintype "passive"))
      (node (ref "MCU_C7") (pin "1") (pinfunction "1_1") (pintype "passive"))
      (node (ref "MCU_C8") (pin "1") (pinfunction "1_1") (pintype "passive"))
      (node (ref "MCU_C9") (pin "1") (pinfunction "1_1") (pintype "passive"))
      (node (ref "MCU_USB_C") (pin "1") (pinfunction "1_1") (pintype "passive"))
      (node (ref "MCU_VDDA_C1") (pin "1") (pinfunction "1_1") (pintype "passive"))
      (node (ref "MCU_VDDA_C2") (pin "1") (pinfunction "1_1") (pintype "passive"))
      (node (ref "NRST_R") (pin "2") (pinfunction "2_2") (pintype "passive"))
      (node (ref "R_REF1") (pin "2") (pinfunction "2_2") (pintype "passive"))
      (node (ref "SWD") (pin "1") (pinfunction "1_1") (pintype "passive"))
      (node (ref "TLV6002") (pin "8") (pinfunction "V+_8") (pintype "power_in"))
      (node (ref "VREG1") (pin "3") (pinfunction "VO_3") (pintype "bidirectional"))
    )
    (net (code "108") (name "VDD_5V") (class "Default")
      (node (ref "CON2") (pin "2") (pinfunction "2_2") (pintype "passive"))
      (node (ref "D_POWER") (pin "A") (pinfunction "A_A") (pintype "passive"))
    )
    (net (code "109") (name "unconnected-(CON1-Pad1)") (class "Default")
      (node (ref "CON1") (pin "1") (pinfunction "1_1") (pintype "passive"))
    )
    (net (code "110") (name "unconnected-(CON1-Pad2)") (class "Default")
      (node (ref "CON1") (pin "2") (pinfunction "2_2") (pintype "passive"))
    )
    (net (code "111") (name "unconnected-(CON1-Pad3)") (class "Default")
      (node (ref "CON1") (pin "3") (pinfunction "3_3") (pintype "passive"))
    )
    (net (code "112") (name "unconnected-(CON1-Pad4)") (class "Default")
      (node (ref "CON1") (pin "4") (pinfunction "4_4") (pintype "passive"))
    )
    (net (code "113") (name "unconnected-(CON1-Pad5)") (class "Default")
      (node (ref "CON1") (pin "5") (pinfunction "5_5") (pintype "passive"))
    )
    (net (code "114") (name "unconnected-(CON1-Pad6)") (class "Default")
      (node (ref "CON1") (pin "6") (pinfunction "6_6") (pintype "passive"))
    )
    (net (code "115") (name "unconnected-(CON1-Pad7)") (class "Default")
      (node (ref "CON1") (pin "7") (pinfunction "7_7") (pintype "passive"))
    )
    (net (code "116") (name "unconnected-(CON1-Pad8)") (class "Default")
      (node (ref "CON1") (pin "8") (pinfunction "8_8") (pintype "passive"))
    )
    (net (code "117") (name "unconnected-(CON1-Pad9)") (class "Default")
      (node (ref "CON1") (pin "9") (pinfunction "9_9") (pintype "passive"))
    )
    (net (code "118") (name "unconnected-(CON1-Pad10)") (class "Default")
      (node (ref "CON1") (pin "10") (pinfunction "10_10") (pintype "passive"))
    )
    (net (code "119") (name "unconnected-(CON1-Pad11)") (class "Default")
      (node (ref "CON1") (pin "11") (pinfunction "11_11") (pintype "passive"))
    )
    (net (code "120") (name "unconnected-(CON1-Pad12)") (class "Default")
      (node (ref "CON1") (pin "12") (pinfunction "12_12") (pintype "passive"))
    )
    (net (code "121") (name "unconnected-(CON1-Pad13)") (class "Default")
      (node (ref "CON1") (pin "13") (pinfunction "13_13") (pintype "passive"))
    )
    (net (code "122") (name "unconnected-(CON1-Pad14)") (class "Default")
      (node (ref "CON1") (pin "14") (pinfunction "14_14") (pintype "passive"))
    )
    (net (code "123") (name "unconnected-(CON1-Pad15)") (class "Default")
      (node (ref "CON1") (pin "15") (pinfunction "15_15") (pintype "passive"))
    )
    (net (code "124") (name "unconnected-(CON1-Pad16)") (class "Default")
      (node (ref "CON1") (pin "16") (pinfunction "16_16") (pintype "passive"))
    )
    (net (code "125") (name "unconnected-(CON1-Pad17)") (class "Default")
      (node (ref "CON1") (pin "17") (pinfunction "17_17") (pintype "passive"))
    )
    (net (code "126") (name "unconnected-(CON1-Pad18)") (class "Default")
      (node (ref "CON1") (pin "18") (pinfunction "18_18") (pintype "passive"))
    )
    (net (code "127") (name "unconnected-(CON1-Pad19)") (class "Default")
      (node (ref "CON1") (pin "19") (pinfunction "19_19") (pintype "passive"))
    )
    (net (code "128") (name "unconnected-(CON1-Pad20)") (class "Default")
      (node (ref "CON1") (pin "20") (pinfunction "20_20") (pintype "passive"))
    )
    (net (code "129") (name "unconnected-(CON1-Pad21)") (class "Default")
      (node (ref "CON1") (pin "21") (pinfunction "21_21") (pintype "passive"))
    )
    (net (code "130") (name "unconnected-(CON1-Pad22)") (class "Default")
      (node (ref "CON1") (pin "22") (pinfunction "22_22") (pintype "passive"))
    )
    (net (code "131") (name "unconnected-(CON1-Pad23)") (class "Default")
      (node (ref "CON1") (pin "23") (pinfunction "23_23") (pintype "passive"))
    )
    (net (code "132") (name "unconnected-(CON1-Pad24)") (class "Default")
      (node (ref "CON1") (pin "24") (pinfunction "24_24") (pintype "passive"))
    )
    (net (code "133") (name "unconnected-(CON1-Pad25)") (class "Default")
      (node (ref "CON1") (pin "25") (pinfunction "25_25") (pintype "passive"))
    )
    (net (code "134") (name "unconnected-(CON1-Pad26)") (class "Default")
      (node (ref "CON1") (pin "26") (pinfunction "26_26") (pintype "passive"))
    )
    (net (code "135") (name "unconnected-(CON1-Pad27)") (class "Default")
      (node (ref "CON1") (pin "27") (pinfunction "27_27") (pintype "passive"))
    )
    (net (code "136") (name "unconnected-(CON1-Pad28)") (class "Default")
      (node (ref "CON1") (pin "28") (pinfunction "28_28") (pintype "passive"))
    )
    (net (code "137") (name "unconnected-(CON1-Pad29)") (class "Default")
      (node (ref "CON1") (pin "29") (pinfunction "29_29") (pintype "passive"))
    )
    (net (code "138") (name "unconnected-(CON1-Pad30)") (class "Default")
      (node (ref "CON1") (pin "30") (pinfunction "30_30") (pintype "passive"))
    )
    (net (code "139") (name "unconnected-(CON1-Pad31)") (class "Default")
      (node (ref "CON1") (pin "31") (pinfunction "31_31") (pintype "passive"))
    )
    (net (code "140") (name "unconnected-(CON1-Pad32)") (class "Default")
      (node (ref "CON1") (pin "32") (pinfunction "32_32") (pintype "passive"))
    )
    (net (code "141") (name "unconnected-(CON1-Pad33)") (class "Default")
      (node (ref "CON1") (pin "33") (pinfunction "33_33") (pintype "passive"))
    )
    (net (code "142") (name "unconnected-(CON1-Pad34)") (class "Default")
      (node (ref "CON1") (pin "34") (pinfunction "34_34") (pintype "passive"))
    )
    (net (code "143") (name "unconnected-(CON1-Pad35)") (class "Default")
      (node (ref "CON1") (pin "35") (pinfunction "35_35") (pintype "passive"))
    )
    (net (code "144") (name "unconnected-(CON1-Pad36)") (class "Default")
      (node (ref "CON1") (pin "36") (pinfunction "36_36") (pintype "passive"))
    )
    (net (code "145") (name "unconnected-(CON1-Pad37)") (class "Default")
      (node (ref "CON1") (pin "37") (pinfunction "37_37") (pintype "passive"))
    )
    (net (code "146") (name "unconnected-(CON1-Pad38)") (class "Default")
      (node (ref "CON1") (pin "38") (pinfunction "38_38") (pintype "passive"))
    )
    (net (code "147") (name "unconnected-(CON1-Pad39)") (class "Default")
      (node (ref "CON1") (pin "39") (pinfunction "39_39") (pintype "passive"))
    )
    (net (code "148") (name "unconnected-(CON1-Pad40)") (class "Default")
      (node (ref "CON1") (pin "40") (pinfunction "40_40") (pintype "passive"))
    )
    (net (code "149") (name "unconnected-(CON1-Pad41)") (class "Default")
      (node (ref "CON1") (pin "41") (pinfunction "41_41") (pintype "passive"))
    )
    (net (code "150") (name "unconnected-(CON1-Pad42)") (class "Default")
      (node (ref "CON1") (pin "42") (pinfunction "42_42") (pintype "passive"))
    )
    (net (code "151") (name "unconnected-(CON1-Pad43)") (class "Default")
      (node (ref "CON1") (pin "43") (pinfunction "43_43") (pintype "passive"))
    )
    (net (code "152") (name "unconnected-(CON1-Pad44)") (class "Default")
      (node (ref "CON1") (pin "44") (pinfunction "44_44") (pintype "passive"))
    )
    (net (code "153") (name "unconnected-(CON1-Pad45)") (class "Default")
      (node (ref "CON1") (pin "45") (pinfunction "45_45") (pintype "passive"))
    )
    (net (code "154") (name "unconnected-(CON1-Pad46)") (class "Default")
      (node (ref "CON1") (pin "46") (pinfunction "46_46") (pintype "passive"))
    )
    (net (code "155") (name "unconnected-(CON1-Pad47)") (class "Default")
      (node (ref "CON1") (pin "47") (pinfunction "47_47") (pintype "passive"))
    )
    (net (code "156") (name "unconnected-(CON1-Pad48)") (class "Default")
      (node (ref "CON1") (pin "48") (pinfunction "48_48") (pintype "passive"))
    )
    (net (code "157") (name "unconnected-(CON1-Pad49)") (class "Default")
      (node (ref "CON1") (pin "49") (pinfunction "49_49") (pintype "passive"))
    )
    (net (code "158") (name "unconnected-(CON1-Pad50)") (class "Default")
      (node (ref "CON1") (pin "50") (pinfunction "50_50") (pintype "passive"))
    )
    (net (code "159") (name "unconnected-(IC1-CBUS0-Pad15)") (class "Default")
      (node (ref "IC1") (pin "15") (pinfunction "CBUS0_15") (pintype "bidirectional"))
    )
    (net (code "160") (name "unconnected-(IC1-CBUS1-Pad14)") (class "Default")
      (node (ref "IC1") (pin "14") (pinfunction "CBUS1_14") (pintype "bidirectional"))
    )
    (net (code "161") (name "unconnected-(IC1-CBUS2-Pad7)") (class "Default")
      (node (ref "IC1") (pin "7") (pinfunction "CBUS2_7") (pintype "bidirectional"))
    )
    (net (code "162") (name "unconnected-(IC1-CBUS3-Pad16)") (class "Default")
      (node (ref "IC1") (pin "16") (pinfunction "CBUS3_16") (pintype "bidirectional"))
    )
    (net (code "163") (name "unconnected-(IC1-~{CTS}-Pad6)") (class "Default")
      (node (ref "IC1") (pin "6") (pinfunction "~{CTS}_6") (pintype "input"))
    )
    (net (code "164") (name "unconnected-(IC1-~{RTS}-Pad2)") (class "Default")
      (node (ref "IC1") (pin "2") (pinfunction "~{RTS}_2") (pintype "output"))
    )
    (net (code "165") (name "unconnected-(MCU1-BOOT0-Pad135)") (class "Default")
      (node (ref "MCU1") (pin "135") (pinfunction "BOOT0_135") (pintype "bidirectional"))
    )
    (net (code "166") (name "unconnected-(MCU1-PA1-Pad38)") (class "Default")
      (node (ref "MCU1") (pin "38") (pinfunction "PA1_38") (pintype "bidirectional"))
    )
    (net (code "167") (name "unconnected-(MCU1-PA10-Pad99)") (class "Default")
      (node (ref "MCU1") (pin "99") (pinfunction "PA10_99") (pintype "bidirectional"))
    )
    (net (code "168") (name "unconnected-(MCU1-PA11-Pad100)") (class "Default")
      (node (ref "MCU1") (pin "100") (pinfunction "PA11_100") (pintype "bidirectional"))
    )
    (net (code "169") (name "unconnected-(MCU1-PA12-Pad101)") (class "Default")
      (node (ref "MCU1") (pin "101") (pinfunction "PA12_101") (pintype "bidirectional"))
    )
    (net (code "170") (name "unconnected-(MCU1-PA15-Pad108)") (class "Default")
      (node (ref "MCU1") (pin "108") (pinfunction "PA15_108") (pintype "bidirectional"))
    )
    (net (code "171") (name "unconnected-(MCU1-PB4-Pad131)") (class "Default")
      (node (ref "MCU1") (pin "131") (pinfunction "PB4_131") (pintype "bidirectional"))
    )
    (net (code "172") (name "unconnected-(MCU1-PB5-Pad132)") (class "Default")
      (node (ref "MCU1") (pin "132") (pinfunction "PB5_132") (pintype "bidirectional"))
    )
    (net (code "173") (name "unconnected-(MCU1-PB6-Pad133)") (class "Default")
      (node (ref "MCU1") (pin "133") (pinfunction "PB6_133") (pintype "bidirectional"))
    )
    (net (code "174") (name "unconnected-(MCU1-PB8-Pad136)") (class "Default")
      (node (ref "MCU1") (pin "136") (pinfunction "PB8_136") (pintype "bidirectional"))
    )
    (net (code "175") (name "unconnected-(MCU1-PB9-Pad137)") (class "Default")
      (node (ref "MCU1") (pin "137") (pinfunction "PB9_137") (pintype "bidirectional"))
    )
    (net (code "176") (name "unconnected-(MCU1-PB10-Pad66)") (class "Default")
      (node (ref "MCU1") (pin "66") (pinfunction "PB10_66") (pintype "bidirectional"))
    )
    (net (code "177") (name "unconnected-(MCU1-PB11-Pad67)") (class "Default")
      (node (ref "MCU1") (pin "67") (pinfunction "PB11_67") (pintype "bidirectional"))
    )
    (net (code "178") (name "unconnected-(MCU1-PB12-Pad72)") (class "Default")
      (node (ref "MCU1") (pin "72") (pinfunction "PB12_72") (pintype "bidirectional"))
    )
    (net (code "179") (name "unconnected-(MCU1-PC2_C-Pad30)") (class "Default")
      (node (ref "MCU1") (pin "30") (pinfunction "PC2_C_30") (pintype "bidirectional"))
    )
    (net (code "180") (name "unconnected-(MCU1-PC3_C-Pad31)") (class "Default")
      (node (ref "MCU1") (pin "31") (pinfunction "PC3_C_31") (pintype "bidirectional"))
    )
    (net (code "181") (name "unconnected-(MCU1-PC5-Pad48)") (class "Default")
      (node (ref "MCU1") (pin "48") (pinfunction "PC5_48") (pintype "bidirectional"))
    )
    (net (code "182") (name "unconnected-(MCU1-PC6-Pad93)") (class "Default")
      (node (ref "MCU1") (pin "93") (pinfunction "PC6_93") (pintype "bidirectional"))
    )
    (net (code "183") (name "unconnected-(MCU1-PC7-Pad94)") (class "Default")
      (node (ref "MCU1") (pin "94") (pinfunction "PC7_94") (pintype "bidirectional"))
    )
    (net (code "184") (name "unconnected-(MCU1-PC8-Pad95)") (class "Default")
      (node (ref "MCU1") (pin "95") (pinfunction "PC8_95") (pintype "bidirectional"))
    )
    (net (code "185") (name "unconnected-(MCU1-PC10-Pad109)") (class "Default")
      (node (ref "MCU1") (pin "109") (pinfunction "PC10_109") (pintype "bidirectional"))
    )
    (net (code "186") (name "unconnected-(MCU1-PC11-Pad110)") (class "Default")
      (node (ref "MCU1") (pin "110") (pinfunction "PC11_110") (pintype "bidirectional"))
    )
    (net (code "187") (name "unconnected-(MCU1-PC12-Pad111)") (class "Default")
      (node (ref "MCU1") (pin "111") (pinfunction "PC12_111") (pintype "bidirectional"))
    )
    (net (code "188") (name "unconnected-(MCU1-PC13-Pad9)") (class "Default")
      (node (ref "MCU1") (pin "9") (pinfunction "PC13_9") (pintype "bidirectional"))
    )
    (net (code "189") (name "unconnected-(MCU1-PC14-OSC32_IN-Pad10)") (class "Default")
      (node (ref "MCU1") (pin "10") (pinfunction "PC14-OSC32_IN_10") (pintype "bidirectional"))
    )
    (net (code "190") (name "unconnected-(MCU1-PC15-OSC32_OUT-Pad11)") (class "Default")
      (node (ref "MCU1") (pin "11") (pinfunction "PC15-OSC32_OUT_11") (pintype "bidirectional"))
    )
    (net (code "191") (name "unconnected-(MCU1-PD2-Pad114)") (class "Default")
      (node (ref "MCU1") (pin "114") (pinfunction "PD2_114") (pintype "bidirectional"))
    )
    (net (code "192") (name "unconnected-(MCU1-PD3-Pad115)") (class "Default")
      (node (ref "MCU1") (pin "115") (pinfunction "PD3_115") (pintype "bidirectional"))
    )
    (net (code "193") (name "unconnected-(MCU1-PD4-Pad116)") (class "Default")
      (node (ref "MCU1") (pin "116") (pinfunction "PD4_116") (pintype "bidirectional"))
    )
    (net (code "194") (name "unconnected-(MCU1-PD5-Pad117)") (class "Default")
      (node (ref "MCU1") (pin "117") (pinfunction "PD5_117") (pintype "bidirectional"))
    )
    (net (code "195") (name "unconnected-(MCU1-PD6-Pad120)") (class "Default")
      (node (ref "MCU1") (pin "120") (pinfunction "PD6_120") (pintype "bidirectional"))
    )
    (net (code "196") (name "unconnected-(MCU1-PD7-Pad121)") (class "Default")
      (node (ref "MCU1") (pin "121") (pinfunction "PD7_121") (pintype "bidirectional"))
    )
    (net (code "197") (name "unconnected-(MCU1-PD13-Pad83)") (class "Default")
      (node (ref "MCU1") (pin "83") (pinfunction "PD13_83") (pintype "bidirectional"))
    )
    (net (code "198") (name "unconnected-(MCU1-PD14-Pad84)") (class "Default")
      (node (ref "MCU1") (pin "84") (pinfunction "PD14_84") (pintype "bidirectional"))
    )
    (net (code "199") (name "unconnected-(MCU1-PD15-Pad85)") (class "Default")
      (node (ref "MCU1") (pin "85") (pinfunction "PD15_85") (pintype "bidirectional"))
    )
    (net (code "200") (name "unconnected-(MCU1-PDR_ON-Pad142)") (class "Default")
      (node (ref "MCU1") (pin "142") (pinfunction "PDR_ON_142") (pintype "bidirectional"))
    )
    (net (code "201") (name "unconnected-(MCU1-PE0-Pad138)") (class "Default")
      (node (ref "MCU1") (pin "138") (pinfunction "PE0_138") (pintype "bidirectional"))
    )
    (net (code "202") (name "unconnected-(MCU1-PE1-Pad139)") (class "Default")
      (node (ref "MCU1") (pin "139") (pinfunction "PE1_139") (pintype "bidirectional"))
    )
    (net (code "203") (name "unconnected-(MCU1-PE2-Pad1)") (class "Default")
      (node (ref "MCU1") (pin "1") (pinfunction "PE2_1") (pintype "bidirectional"))
    )
    (net (code "204") (name "unconnected-(MCU1-PE3-Pad2)") (class "Default")
      (node (ref "MCU1") (pin "2") (pinfunction "PE3_2") (pintype "bidirectional"))
    )
    (net (code "205") (name "unconnected-(MCU1-PE4-Pad3)") (class "Default")
      (node (ref "MCU1") (pin "3") (pinfunction "PE4_3") (pintype "bidirectional"))
    )
    (net (code "206") (name "unconnected-(MCU1-PE5-Pad4)") (class "Default")
      (node (ref "MCU1") (pin "4") (pinfunction "PE5_4") (pintype "bidirectional"))
    )
    (net (code "207") (name "unconnected-(MCU1-PE6-Pad5)") (class "Default")
      (node (ref "MCU1") (pin "5") (pinfunction "PE6_5") (pintype "bidirectional"))
    )
    (net (code "208") (name "unconnected-(MCU1-PE9-Pad59)") (class "Default")
      (node (ref "MCU1") (pin "59") (pinfunction "PE9_59") (pintype "bidirectional"))
    )
    (net (code "209") (name "unconnected-(MCU1-PE10-Pad60)") (class "Default")
      (node (ref "MCU1") (pin "60") (pinfunction "PE10_60") (pintype "bidirectional"))
    )
    (net (code "210") (name "unconnected-(MCU1-PE11-Pad61)") (class "Default")
      (node (ref "MCU1") (pin "61") (pinfunction "PE11_61") (pintype "bidirectional"))
    )
    (net (code "211") (name "unconnected-(MCU1-PF6-Pad20)") (class "Default")
      (node (ref "MCU1") (pin "20") (pinfunction "PF6_20") (pintype "bidirectional"))
    )
    (net (code "212") (name "unconnected-(MCU1-PG6-Pad86)") (class "Default")
      (node (ref "MCU1") (pin "86") (pinfunction "PG6_86") (pintype "bidirectional"))
    )
    (net (code "213") (name "unconnected-(MCU1-PG11-Pad124)") (class "Default")
      (node (ref "MCU1") (pin "124") (pinfunction "PG11_124") (pintype "bidirectional"))
    )
    (net (code "214") (name "unconnected-(MCU1-PG12-Pad125)") (class "Default")
      (node (ref "MCU1") (pin "125") (pinfunction "PG12_125") (pintype "bidirectional"))
    )
    (net (code "215") (name "unconnected-(MCU1-PG14-Pad127)") (class "Default")
      (node (ref "MCU1") (pin "127") (pinfunction "PG14_127") (pintype "bidirectional"))
    )
    (net (code "216") (name "unconnected-(MCU1-VBAT-Pad8)") (class "Default")
      (node (ref "MCU1") (pin "8") (pinfunction "VBAT_8") (pintype "bidirectional"))
    )
    (net (code "217") (name "unconnected-(MCU1-VDD33USB-Pad91)") (class "Default")
      (node (ref "MCU1") (pin "91") (pinfunction "VDD33USB_91") (pintype "bidirectional"))
    )
    (net (code "218") (name "unconnected-(MCU1-VDD50USB-Pad90)") (class "Default")
      (node (ref "MCU1") (pin "90") (pinfunction "VDD50USB_90") (pintype "bidirectional"))
    )
    (net (code "219") (name "unconnected-(MCU1-VDDA-Pad36)") (class "Default")
      (node (ref "MCU1") (pin "36") (pinfunction "VDDA_36") (pintype "bidirectional"))
    )
    (net (code "220") (name "unconnected-(MCU1-VDDLDO-Pad70)") (class "Default")
      (node (ref "MCU1") (pin "70") (pinfunction "VDDLDO_70") (pintype "bidirectional"))
    )
    (net (code "221") (name "unconnected-(MCU1-VDDLDO-Pad105)") (class "Default")
      (node (ref "MCU1") (pin "105") (pinfunction "VDDLDO_105") (pintype "bidirectional"))
    )
    (net (code "222") (name "unconnected-(MCU1-VDDLDO-Pad143)") (class "Default")
      (node (ref "MCU1") (pin "143") (pinfunction "VDDLDO_143") (pintype "bidirectional"))
    )
    (net (code "223") (name "unconnected-(MCU1-VDDSMPS-Pad16)") (class "Default")
      (node (ref "MCU1") (pin "16") (pinfunction "VDDSMPS_16") (pintype "bidirectional"))
    )
    (net (code "224") (name "unconnected-(MCU1-VFBSMPS-Pad17)") (class "Default")
      (node (ref "MCU1") (pin "17") (pinfunction "VFBSMPS_17") (pintype "bidirectional"))
    )
    (net (code "225") (name "unconnected-(MCU1-VLXSMPS-Pad15)") (class "Default")
      (node (ref "MCU1") (pin "15") (pinfunction "VLXSMPS_15") (pintype "bidirectional"))
    )
    (net (code "226") (name "unconnected-(MCU1-VSSA-Pad34)") (class "Default")
      (node (ref "MCU1") (pin "34") (pinfunction "VSSA_34") (pintype "bidirectional"))
    )
  )
)
